# ct_frontend.net
KiCad netlist of a schematic drawn in Altium Designer
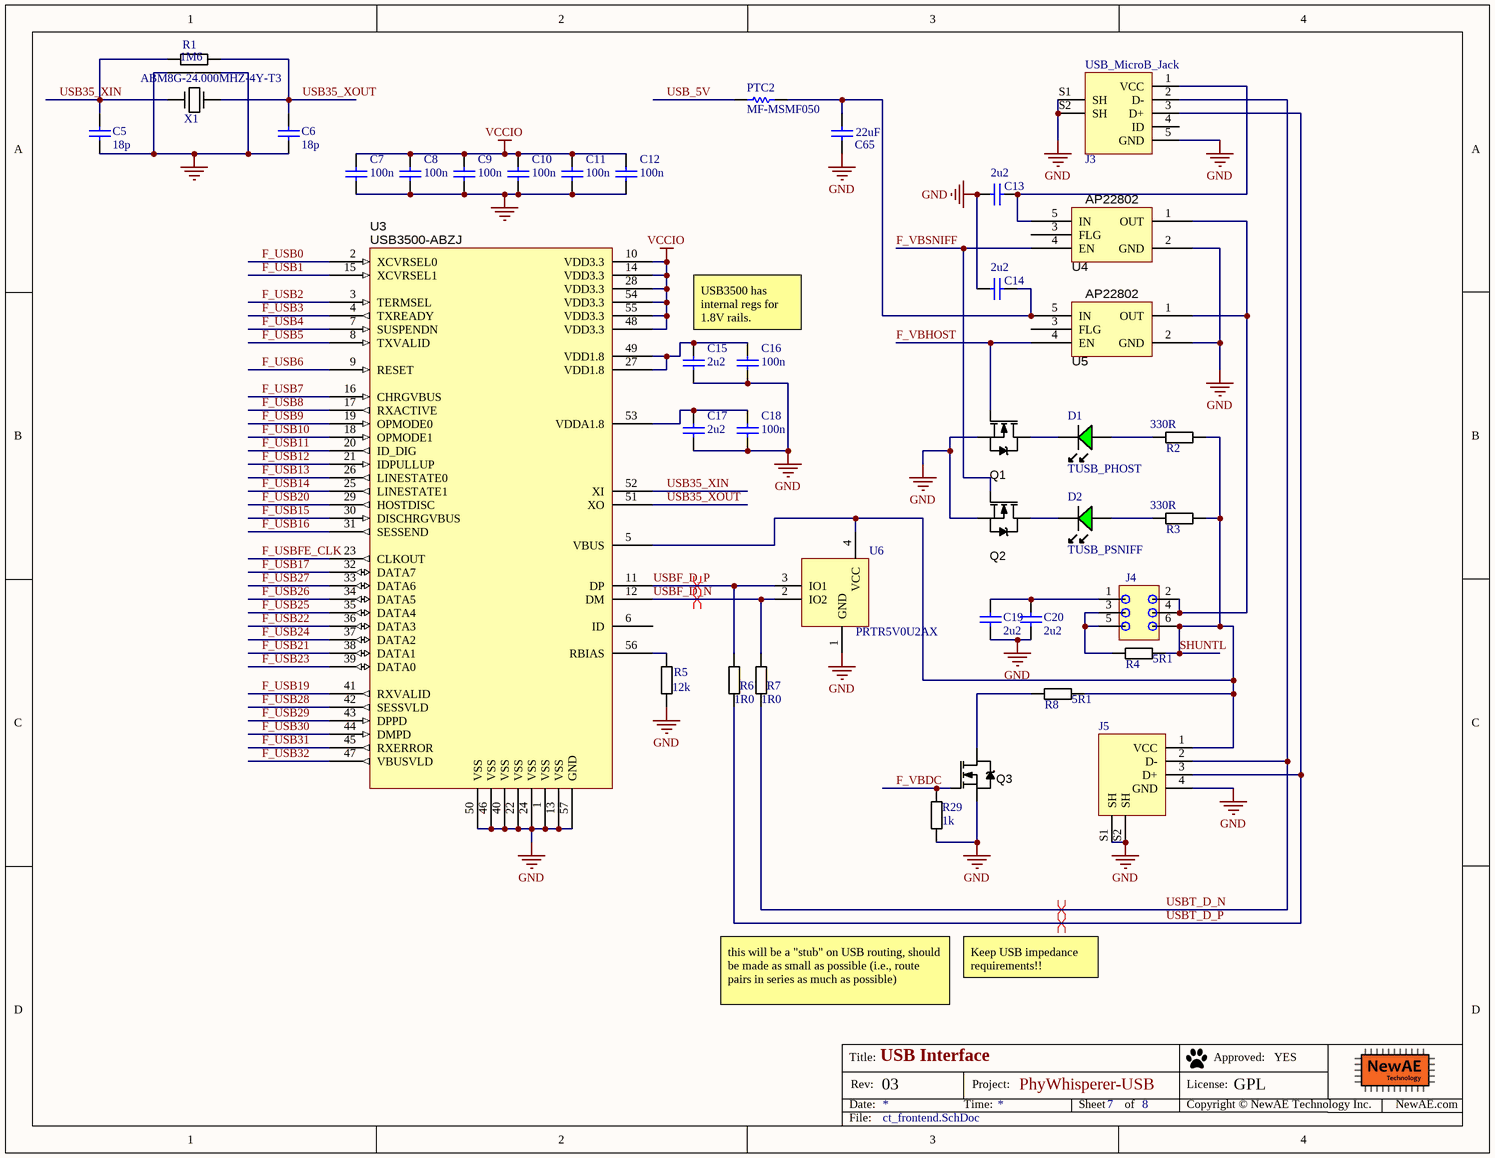
[diagram p0: ct_frontend.SchDoc]

(export (version "E")
  (design (tool "Eeschema 10.0.6"))
  (components
    (comp (ref "C5")
      (value "18p")
      (footprint "CAPC0402_M")
      (description "18p, 0402")
      (fields (field (name "PART NUMBER") "CCHIP-18p-0402"))
      (libsource (lib "NewAE_AltiumLib") (part "CAP"))
    )
    (comp (ref "C6")
      (value "18p")
      (footprint "CAPC0402_M")
      (description "18p, 0402")
      (fields (field (name "PART NUMBER") "CCHIP-18p-0402"))
      (libsource (lib "NewAE_AltiumLib") (part "CAP"))
    )
    (comp (ref "C7")
      (value "100n")
      (footprint "CAPC0603_M")
      (description "100n, 0603")
      (fields (field (name "PART NUMBER") "CCHIP-100n-0603"))
      (libsource (lib "NewAE_AltiumLib") (part "CAP"))
    )
    (comp (ref "C8")
      (value "100n")
      (footprint "CAPC0603_M")
      (description "100n, 0603")
      (fields (field (name "PART NUMBER") "CCHIP-100n-0603"))
      (libsource (lib "NewAE_AltiumLib") (part "CAP"))
    )
    (comp (ref "C9")
      (value "100n")
      (footprint "CAPC0603_M")
      (description "100n, 0603")
      (fields (field (name "PART NUMBER") "CCHIP-100n-0603"))
      (libsource (lib "NewAE_AltiumLib") (part "CAP"))
    )
    (comp (ref "C10")
      (value "100n")
      (footprint "CAPC0603_M")
      (description "100n, 0603")
      (fields (field (name "PART NUMBER") "CCHIP-100n-0603"))
      (libsource (lib "NewAE_AltiumLib") (part "CAP"))
    )
    (comp (ref "C11")
      (value "100n")
      (footprint "CAPC0603_M")
      (description "100n, 0603")
      (fields (field (name "PART NUMBER") "CCHIP-100n-0603"))
      (libsource (lib "NewAE_AltiumLib") (part "CAP"))
    )
    (comp (ref "C12")
      (value "100n")
      (footprint "CAPC0603_M")
      (description "100n, 0603")
      (fields (field (name "PART NUMBER") "CCHIP-100n-0603"))
      (libsource (lib "NewAE_AltiumLib") (part "CAP"))
    )
    (comp (ref "C13")
      (value "2u2")
      (footprint "CAPC0603_M")
      (description "2u2, 0603")
      (fields (field (name "PART NUMBER") "CCHIP-2u2-0603"))
      (libsource (lib "NewAE_AltiumLib") (part "CAP"))
    )
    (comp (ref "C14")
      (value "2u2")
      (footprint "CAPC0603_M")
      (description "2u2, 0603")
      (fields (field (name "PART NUMBER") "CCHIP-2u2-0603"))
      (libsource (lib "NewAE_AltiumLib") (part "CAP"))
    )
    (comp (ref "C15")
      (value "2u2")
      (footprint "CAPC0603_M")
      (description "2u2, 0603")
      (fields (field (name "PART NUMBER") "CCHIP-2u2-0603"))
      (libsource (lib "NewAE_AltiumLib") (part "CAP"))
    )
    (comp (ref "C16")
      (value "100n")
      (footprint "CAPC0603_M")
      (description "100n, 0603")
      (fields (field (name "PART NUMBER") "CCHIP-100n-0603"))
      (libsource (lib "NewAE_AltiumLib") (part "CAP"))
    )
    (comp (ref "C17")
      (value "2u2")
      (footprint "CAPC0603_M")
      (description "2u2, 0603")
      (fields (field (name "PART NUMBER") "CCHIP-2u2-0603"))
      (libsource (lib "NewAE_AltiumLib") (part "CAP"))
    )
    (comp (ref "C18")
      (value "100n")
      (footprint "CAPC0603_M")
      (description "100n, 0603")
      (fields (field (name "PART NUMBER") "CCHIP-100n-0603"))
      (libsource (lib "NewAE_AltiumLib") (part "CAP"))
    )
    (comp (ref "C19")
      (value "2u2")
      (footprint "CAPC0603_M")
      (description "2u2, 0603")
      (fields (field (name "PART NUMBER") "CCHIP-2u2-0603"))
      (libsource (lib "NewAE_AltiumLib") (part "CAP"))
    )
    (comp (ref "C20")
      (value "2u2")
      (footprint "CAPC0603_M")
      (description "2u2, 0603")
      (fields (field (name "PART NUMBER") "CCHIP-2u2-0603"))
      (libsource (lib "NewAE_AltiumLib") (part "CAP"))
    )
    (comp (ref "C65")
      (value "22uF")
      (footprint "CAPC0805_M")
      (description "22u, 16V, 0805, Ceramic")
      (fields (field (name "PART NUMBER") "CCHIP-22u-0805-16V") (field (name "TOLERANCE") "20%"))
      (libsource (lib "NewAE_AltiumLib") (part "CAP"))
    )
    (comp (ref "D1")
      (value "TUSB_PHOST")
      (footprint "LED-0603-GREEN")
      (description "Chip LED, Green")
      (fields (field (name "PART NUMBER") "LEDCHIP_0603_GREEN"))
      (libsource (lib "NewAE_AltiumLib") (part "LED_GREEN"))
    )
    (comp (ref "D2")
      (value "TUSB_PSNIFF")
      (footprint "LED-0603-GREEN")
      (description "Chip LED, Green")
      (fields (field (name "PART NUMBER") "LEDCHIP_0603_GREEN"))
      (libsource (lib "NewAE_AltiumLib") (part "LED_GREEN"))
    )
    (comp (ref "J3")
      (value "USB_MicroB_Jack")
      (footprint "ZX62D-B-5P8(30)")
      (description "CONN RCPT USB MICRO B SMD")
      (fields (field (name "PART NUMBER") "ZX62D-B-5P8(30)"))
      (libsource (lib "NewAE_AltiumLib") (part "USB_5PIN_2SHIELD"))
    )
    (comp (ref "J4")
      (value "TSW-103-08-F-D-RA")
      (footprint "HDR_6PIN_2ROW_RA_UNSHROUDED")
      (description "2x3 Header, R/A, Unshrouded")
      (fields (field (name "PART NUMBER") "HDR_6PIN_2ROW_RA_UNSHROUDED"))
      (libsource (lib "NewAE_AltiumLib") (part "CON6_2ROW"))
    )
    (comp (ref "J5")
      (value "USB-A-S-F-W-TH")
      (footprint "USB-A-S-F-W-TH")
      (description "Female USB-A")
      (libsource (lib "NewAE_AltiumLib") (part "USB_4PIN_2SHIELD"))
    )
    (comp (ref "PTC2")
      (value "MF-MSMF050")
      (footprint "BOUR-MF-MSMF050-2_V")
      (description "MF-MSMF Series - PTC Resettable Fuse, 15 V Max, 0.15 Ohm Min, -40 to 85 degC, RoHS, Reel")
      (fields (field (name "MANUFACTURER") "Bourns"))
      (libsource (lib "Altium Content Vault") (part "CMP-0280-00002-2"))
    )
    (comp (ref "Q1")
      (value "DMN3200U-7")
      (footprint "SOT95P245X110-3M")
      (description "MOSFET N-CH 30V 2.2A SOT23-3")
      (libsource (lib "NewAE_AltiumLib") (part "MOSFET_N_GSD"))
    )
    (comp (ref "Q2")
      (value "DMN3200U-7")
      (footprint "SOT95P245X110-3M")
      (description "MOSFET N-CH 30V 2.2A SOT23-3")
      (libsource (lib "NewAE_AltiumLib") (part "MOSFET_N_GSD"))
    )
    (comp (ref "Q3")
      (value "DMN3200U-7")
      (footprint "SOT95P245X110-3M")
      (description "MOSFET N-CH 30V 2.2A SOT23-3")
      (libsource (lib "NewAE_AltiumLib") (part "MOSFET_N_GSD"))
    )
    (comp (ref "R1")
      (value "1M6")
      (footprint "RESC1608X55N")
      (description "1M6 res, 0603, 1%, 1/10W")
      (fields (field (name "PART NUMBER") "RCHIP-1M6-0603") (field (name "TOLERANCE") "1%"))
      (libsource (lib "NewAE_AltiumLib") (part "RES-EU"))
    )
    (comp (ref "R2")
      (value "330R")
      (footprint "RESC1608X55N")
      (description "330R res, 0603, 1%, 1/10W")
      (fields (field (name "PART NUMBER") "RCHIP-330R-0603") (field (name "TOLERANCE") "1%"))
      (libsource (lib "NewAE_AltiumLib") (part "RES-EU"))
    )
    (comp (ref "R3")
      (value "330R")
      (footprint "RESC1608X55N")
      (description "330R res, 0603, 1%, 1/10W")
      (fields (field (name "PART NUMBER") "RCHIP-330R-0603") (field (name "TOLERANCE") "1%"))
      (libsource (lib "NewAE_AltiumLib") (part "RES-EU"))
    )
    (comp (ref "R4")
      (value "5R1")
      (footprint "RESC2012X70N")
      (description "5R1  res, 0805, 1%")
      (fields (field (name "PART NUMBER") "RCHIP-5R1-0805"))
      (libsource (lib "NewAE_AltiumLib") (part "RES-EU"))
    )
    (comp (ref "R5")
      (value "12k")
      (footprint "RESC1608X55N")
      (description "12k res, 0603, 1%, 1/10W")
      (fields (field (name "PART NUMBER") "RCHIP-12K-0603") (field (name "TOLERANCE") "1%"))
      (libsource (lib "") (part "RES-EU_1"))
    )
    (comp (ref "R6")
      (value "1R0")
      (footprint "RESC1608X55N")
      (description "1R0 res, 0603, 1%, 1/10W")
      (fields (field (name "PART NUMBER") "RCHIP-1R0-0603") (field (name "TOLERANCE") "1%"))
      (libsource (lib "") (part "RES-EU_1"))
    )
    (comp (ref "R7")
      (value "1R0")
      (footprint "RESC1608X55N")
      (description "1R0 res, 0603, 1%, 1/10W")
      (fields (field (name "PART NUMBER") "RCHIP-1R0-0603") (field (name "TOLERANCE") "1%"))
      (libsource (lib "") (part "RES-EU_1"))
    )
    (comp (ref "R8")
      (value "5R1")
      (footprint "RESC2012X70N")
      (description "5R1  res, 0805, 1%")
      (fields (field (name "PART NUMBER") "RCHIP-5R1-0805"))
      (libsource (lib "NewAE_AltiumLib") (part "RES-EU"))
    )
    (comp (ref "R29")
      (value "1k")
      (footprint "RESC1608X55N")
      (description "1k res, 0603, 1%, 1/10W")
      (fields (field (name "PART NUMBER") "RCHIP-1K-0603") (field (name "TOLERANCE") "1%"))
      (libsource (lib "") (part "RES-EU_2"))
    )
    (comp (ref "U3")
      (value "USB3500-ABZJ")
      (footprint "QFN50P800X800X100_HS-57M")
      (description "USB Phy, UTMI 3+")
      (fields (field (name "PART NUMBER") "USB3500") (field (name "CREATED BY") "D.GODDARD"))
      (libsource (lib "NewAE_AltiumLib") (part "USB3500"))
    )
    (comp (ref "U4")
      (value "AP22802")
      (footprint "SOT23-5P95_285X145L45X40")
      (description "USB Power Switch, Digital IC")
      (fields (field (name "CREATED BY") "D.GODDARD"))
      (libsource (lib "NewAE_AltiumLib") (part "AP22802"))
    )
    (comp (ref "U5")
      (value "AP22802")
      (footprint "SOT23-5P95_285X145L45X40")
      (description "USB Power Switch, Digital IC")
      (fields (field (name "CREATED BY") "D.GODDARD"))
      (libsource (lib "NewAE_AltiumLib") (part "AP22802"))
    )
    (comp (ref "U6")
      (value "PRTR5V0U2AX")
      (footprint "SOT143B")
      (description "USB 2.0 high-speed ESD")
      (libsource (lib "NewAE_AltiumLib") (part "PRTR5V0U2AX"))
    )
    (comp (ref "X1")
      (value "ABM8G-24.000MHZ-4Y-T3")
      (footprint "ABM8G")
      (description "CRYSTAL 24.0000MHZ 10PF SMD")
      (libsource (lib "NewAE_AltiumLib") (part "XTAL_4PIN_13"))
    )
  )
  (nets
    (net (code "1") (name "/F_USB0") (class "Default")
      (node (ref "U3") (pin "2") (pinfunction "XCVRSEL0_2") (pintype "input"))
    )
    (net (code "2") (name "/F_USB1") (class "Default")
      (node (ref "U3") (pin "15") (pinfunction "XCVRSEL1_15") (pintype "input"))
    )
    (net (code "3") (name "/F_USB2") (class "Default")
      (node (ref "U3") (pin "3") (pinfunction "TERMSEL_3") (pintype "input"))
    )
    (net (code "4") (name "/F_USB3") (class "Default")
      (node (ref "U3") (pin "4") (pinfunction "TXREADY_4") (pintype "output"))
    )
    (net (code "5") (name "/F_USB4") (class "Default")
      (node (ref "U3") (pin "7") (pinfunction "SUSPENDN_7") (pintype "input"))
    )
    (net (code "6") (name "/F_USB5") (class "Default")
      (node (ref "U3") (pin "8") (pinfunction "TXVALID_8") (pintype "input"))
    )
    (net (code "7") (name "/F_USB6") (class "Default")
      (node (ref "U3") (pin "9") (pinfunction "RESET_9") (pintype "input"))
    )
    (net (code "8") (name "/F_USB7") (class "Default")
      (node (ref "U3") (pin "16") (pinfunction "CHRGVBUS_16") (pintype "input"))
    )
    (net (code "9") (name "/F_USB8") (class "Default")
      (node (ref "U3") (pin "17") (pinfunction "RXACTIVE_17") (pintype "output"))
    )
    (net (code "10") (name "/F_USB9") (class "Default")
      (node (ref "U3") (pin "19") (pinfunction "OPMODE0_19") (pintype "input"))
    )
    (net (code "11") (name "/F_USB10") (class "Default")
      (node (ref "U3") (pin "18") (pinfunction "OPMODE1_18") (pintype "input"))
    )
    (net (code "12") (name "/F_USB11") (class "Default")
      (node (ref "U3") (pin "20") (pinfunction "ID_DIG_20") (pintype "output"))
    )
    (net (code "13") (name "/F_USB12") (class "Default")
      (node (ref "U3") (pin "21") (pinfunction "IDPULLUP_21") (pintype "input"))
    )
    (net (code "14") (name "/F_USB13") (class "Default")
      (node (ref "U3") (pin "26") (pinfunction "LINESTATE0_26") (pintype "output"))
    )
    (net (code "15") (name "/F_USB14") (class "Default")
      (node (ref "U3") (pin "25") (pinfunction "LINESTATE1_25") (pintype "output"))
    )
    (net (code "16") (name "/F_USB15") (class "Default")
      (node (ref "U3") (pin "30") (pinfunction "DISCHRGVBUS_30") (pintype "input"))
    )
    (net (code "17") (name "/F_USB16") (class "Default")
      (node (ref "U3") (pin "31") (pinfunction "SESSEND_31") (pintype "output"))
    )
    (net (code "18") (name "/F_USB17") (class "Default")
      (node (ref "U3") (pin "32") (pinfunction "DATA7_32") (pintype "bidirectional"))
    )
    (net (code "19") (name "/F_USB19") (class "Default")
      (node (ref "U3") (pin "41") (pinfunction "RXVALID_41") (pintype "output"))
    )
    (net (code "20") (name "/F_USB20") (class "Default")
      (node (ref "U3") (pin "29") (pinfunction "HOSTDISC_29") (pintype "output"))
    )
    (net (code "21") (name "/F_USB21") (class "Default")
      (node (ref "U3") (pin "38") (pinfunction "DATA1_38") (pintype "bidirectional"))
    )
    (net (code "22") (name "/F_USB22") (class "Default")
      (node (ref "U3") (pin "36") (pinfunction "DATA3_36") (pintype "bidirectional"))
    )
    (net (code "23") (name "/F_USB23") (class "Default")
      (node (ref "U3") (pin "39") (pinfunction "DATA0_39") (pintype "bidirectional"))
    )
    (net (code "24") (name "/F_USB24") (class "Default")
      (node (ref "U3") (pin "37") (pinfunction "DATA2_37") (pintype "bidirectional"))
    )
    (net (code "25") (name "/F_USB25") (class "Default")
      (node (ref "U3") (pin "35") (pinfunction "DATA4_35") (pintype "bidirectional"))
    )
    (net (code "26") (name "/F_USB26") (class "Default")
      (node (ref "U3") (pin "34") (pinfunction "DATA5_34") (pintype "bidirectional"))
    )
    (net (code "27") (name "/F_USB27") (class "Default")
      (node (ref "U3") (pin "33") (pinfunction "DATA6_33") (pintype "bidirectional"))
    )
    (net (code "28") (name "/F_USB28") (class "Default")
      (node (ref "U3") (pin "42") (pinfunction "SESSVLD_42") (pintype "output"))
    )
    (net (code "29") (name "/F_USB29") (class "Default")
      (node (ref "U3") (pin "43") (pinfunction "DPPD_43") (pintype "input"))
    )
    (net (code "30") (name "/F_USB30") (class "Default")
      (node (ref "U3") (pin "44") (pinfunction "DMPD_44") (pintype "input"))
    )
    (net (code "31") (name "/F_USB31") (class "Default")
      (node (ref "U3") (pin "45") (pinfunction "RXERROR_45") (pintype "output"))
    )
    (net (code "32") (name "/F_USB32") (class "Default")
      (node (ref "U3") (pin "47") (pinfunction "VBUSVLD_47") (pintype "output"))
    )
    (net (code "33") (name "/F_USBFE_CLK") (class "Default")
      (node (ref "U3") (pin "23") (pinfunction "CLKOUT_23") (pintype "output"))
    )
    (net (code "34") (name "/F_VBDC") (class "Default")
      (node (ref "Q3") (pin "1") (pinfunction "G_1") (pintype "passive"))
      (node (ref "R29") (pin "2") (pinfunction "2_2") (pintype "passive"))
    )
    (net (code "35") (name "/F_VBHOST") (class "Default")
      (node (ref "Q1") (pin "1") (pinfunction "G_1") (pintype "passive"))
      (node (ref "U5") (pin "4") (pinfunction "EN_4") (pintype "passive"))
    )
    (net (code "36") (name "/F_VBSNIFF") (class "Default")
      (node (ref "Q2") (pin "1") (pinfunction "G_1") (pintype "passive"))
      (node (ref "U4") (pin "4") (pinfunction "EN_4") (pintype "passive"))
    )
    (net (code "37") (name "/SHUNTL") (class "Default")
      (node (ref "J4") (pin "6") (pinfunction "6_6") (pintype "passive"))
      (node (ref "J5") (pin "1") (pinfunction "VCC_1") (pintype "passive"))
      (node (ref "R2") (pin "2") (pinfunction "2_2") (pintype "passive"))
      (node (ref "R3") (pin "2") (pinfunction "2_2") (pintype "passive"))
      (node (ref "R4") (pin "2") (pinfunction "2_2") (pintype "passive"))
      (node (ref "R8") (pin "2") (pinfunction "2_2") (pintype "passive"))
      (node (ref "U3") (pin "5") (pinfunction "VBUS_5") (pintype "passive"))
      (node (ref "U6") (pin "4") (pinfunction "VCC_4") (pintype "power_in"))
    )
    (net (code "38") (name "/USB35_XIN") (class "Default")
      (node (ref "C5") (pin "1") (pinfunction "1_1") (pintype "passive"))
      (node (ref "R1") (pin "1") (pinfunction "1_1") (pintype "passive"))
      (node (ref "U3") (pin "52") (pinfunction "XI_52") (pintype "passive"))
      (node (ref "X1") (pin "1") (pinfunction "IN_1") (pintype "passive"))
    )
    (net (code "39") (name "/USB35_XOUT") (class "Default")
      (node (ref "C6") (pin "1") (pinfunction "1_1") (pintype "passive"))
      (node (ref "R1") (pin "2") (pinfunction "2_2") (pintype "passive"))
      (node (ref "U3") (pin "51") (pinfunction "XO_51") (pintype "passive"))
      (node (ref "X1") (pin "3") (pinfunction "OUT_3") (pintype "passive"))
    )
    (net (code "40") (name "/USBF_D_N") (class "Default")
      (node (ref "R7") (pin "1") (pinfunction "1_1") (pintype "passive"))
      (node (ref "U3") (pin "12") (pinfunction "DM_12") (pintype "passive"))
      (node (ref "U6") (pin "2") (pinfunction "IO2_2") (pintype "power_in"))
    )
    (net (code "41") (name "/USBF_D_P") (class "Default")
      (node (ref "R6") (pin "1") (pinfunction "1_1") (pintype "passive"))
      (node (ref "U3") (pin "11") (pinfunction "DP_11") (pintype "passive"))
      (node (ref "U6") (pin "3") (pinfunction "IO1_3") (pintype "power_in"))
    )
    (net (code "42") (name "/USBT_D_N") (class "Default")
      (node (ref "J3") (pin "2") (pinfunction "D-_2") (pintype "passive"))
      (node (ref "J5") (pin "2") (pinfunction "D-_2") (pintype "passive"))
      (node (ref "R7") (pin "2") (pinfunction "2_2") (pintype "passive"))
    )
    (net (code "43") (name "/USBT_D_P") (class "Default")
      (node (ref "J3") (pin "3") (pinfunction "D+_3") (pintype "passive"))
      (node (ref "J5") (pin "3") (pinfunction "D+_3") (pintype "passive"))
      (node (ref "R6") (pin "2") (pinfunction "2_2") (pintype "passive"))
    )
    (net (code "44") (name "/USB_5V") (class "Default")
      (node (ref "PTC2") (pin "1") (pinfunction "1_1") (pintype "passive"))
    )
    (net (code "45") (name "GND") (class "Default")
      (node (ref "C10") (pin "2") (pinfunction "2_2") (pintype "passive"))
      (node (ref "C11") (pin "2") (pinfunction "2_2") (pintype "passive"))
      (node (ref "C12") (pin "2") (pinfunction "2_2") (pintype "passive"))
      (node (ref "C13") (pin "1") (pinfunction "1_1") (pintype "passive"))
      (node (ref "C14") (pin "1") (pinfunction "1_1") (pintype "passive"))
      (node (ref "C15") (pin "2") (pinfunction "2_2") (pintype "passive"))
      (node (ref "C16") (pin "2") (pinfunction "2_2") (pintype "passive"))
      (node (ref "C17") (pin "2") (pinfunction "2_2") (pintype "passive"))
      (node (ref "C18") (pin "2") (pinfunction "2_2") (pintype "passive"))
      (node (ref "C19") (pin "1") (pinfunction "1_1") (pintype "passive"))
      (node (ref "C20") (pin "1") (pinfunction "1_1") (pintype "passive"))
      (node (ref "C5") (pin "2") (pinfunction "2_2") (pintype "passive"))
      (node (ref "C6") (pin "2") (pinfunction "2_2") (pintype "passive"))
      (node (ref "C65") (pin "2") (pinfunction "2_2") (pintype "passive"))
      (node (ref "C7") (pin "2") (pinfunction "2_2") (pintype "passive"))
      (node (ref "C8") (pin "2") (pinfunction "2_2") (pintype "passive"))
      (node (ref "C9") (pin "2") (pinfunction "2_2") (pintype "passive"))
      (node (ref "J3") (pin "5") (pinfunction "GND_5") (pintype "power_in"))
      (node (ref "J3") (pin "S1") (pinfunction "SH_S1") (pintype "passive"))
      (node (ref "J3") (pin "S2") (pinfunction "SH_S2") (pintype "passive"))
      (node (ref "J5") (pin "4") (pinfunction "GND_4") (pintype "power_in"))
      (node (ref "J5") (pin "S1") (pinfunction "SH_S1") (pintype "passive"))
      (node (ref "J5") (pin "S2") (pinfunction "SH_S2") (pintype "passive"))
      (node (ref "Q1") (pin "2") (pinfunction "S_2") (pintype "passive"))
      (node (ref "Q2") (pin "2") (pinfunction "S_2") (pintype "passive"))
      (node (ref "Q3") (pin "2") (pinfunction "S_2") (pintype "passive"))
      (node (ref "R29") (pin "1") (pinfunction "1_1") (pintype "passive"))
      (node (ref "R5") (pin "2") (pinfunction "2_2") (pintype "passive"))
      (node (ref "U3") (pin "1") (pinfunction "VSS_1") (pintype "passive"))
      (node (ref "U3") (pin "13") (pinfunction "VSS_13") (pintype "passive"))
      (node (ref "U3") (pin "22") (pinfunction "VSS_22") (pintype "passive"))
      (node (ref "U3") (pin "24") (pinfunction "VSS_24") (pintype "passive"))
      (node (ref "U3") (pin "40") (pinfunction "VSS_40") (pintype "passive"))
      (node (ref "U3") (pin "46") (pinfunction "VSS_46") (pintype "passive"))
      (node (ref "U3") (pin "50") (pinfunction "VSS_50") (pintype "passive"))
      (node (ref "U3") (pin "57") (pinfunction "GND_57") (pintype "passive"))
      (node (ref "U4") (pin "2") (pinfunction "GND_2") (pintype "passive"))
      (node (ref "U5") (pin "2") (pinfunction "GND_2") (pintype "passive"))
      (node (ref "U6") (pin "1") (pinfunction "GND_1") (pintype "power_in"))
      (node (ref "X1") (pin "2") (pinfunction "GND_2") (pintype "power_in"))
      (node (ref "X1") (pin "4") (pinfunction "GND_4") (pintype "power_in"))
    )
    (net (code "46") (name "Net-(C15-Pad1)") (class "Default")
      (node (ref "C15") (pin "1") (pinfunction "1_1") (pintype "passive"))
      (node (ref "C16") (pin "1") (pinfunction "1_1") (pintype "passive"))
      (node (ref "U3") (pin "27") (pinfunction "VDD1.8_27") (pintype "passive"))
      (node (ref "U3") (pin "49") (pinfunction "VDD1.8_49") (pintype "passive"))
    )
    (net (code "47") (name "Net-(C19-Pad2)") (class "Default")
      (node (ref "C19") (pin "2") (pinfunction "2_2") (pintype "passive"))
      (node (ref "C20") (pin "2") (pinfunction "2_2") (pintype "passive"))
      (node (ref "J4") (pin "1") (pinfunction "1_1") (pintype "passive"))
    )
    (net (code "48") (name "Net-(D1-PadA)") (class "Default")
      (node (ref "D1") (pin "A") (pinfunction "A_A") (pintype "passive"))
      (node (ref "R2") (pin "1") (pinfunction "1_1") (pintype "passive"))
    )
    (net (code "49") (name "Net-(D2-PadA)") (class "Default")
      (node (ref "D2") (pin "A") (pinfunction "A_A") (pintype "passive"))
      (node (ref "R3") (pin "1") (pinfunction "1_1") (pintype "passive"))
    )
    (net (code "50") (name "Net-(J3-VCC)") (class "Default")
      (node (ref "C13") (pin "2") (pinfunction "2_2") (pintype "passive"))
      (node (ref "J3") (pin "1") (pinfunction "VCC_1") (pintype "passive"))
      (node (ref "U4") (pin "5") (pinfunction "IN_5") (pintype "passive"))
    )
    (net (code "51") (name "Net-(J4-Pad3)") (class "Default")
      (node (ref "J4") (pin "3") (pinfunction "3_3") (pintype "passive"))
      (node (ref "J4") (pin "5") (pinfunction "5_5") (pintype "passive"))
      (node (ref "R4") (pin "1") (pinfunction "1_1") (pintype "passive"))
    )
    (net (code "52") (name "Net-(Q1-D)") (class "Default")
      (node (ref "D1") (pin "K") (pinfunction "K_K") (pintype "passive"))
      (node (ref "Q1") (pin "3") (pinfunction "D_3") (pintype "passive"))
    )
    (net (code "53") (name "Net-(Q2-D)") (class "Default")
      (node (ref "D2") (pin "K") (pinfunction "K_K") (pintype "passive"))
      (node (ref "Q2") (pin "3") (pinfunction "D_3") (pintype "passive"))
    )
    (net (code "54") (name "Net-(Q3-D)") (class "Default")
      (node (ref "Q3") (pin "3") (pinfunction "D_3") (pintype "passive"))
      (node (ref "R8") (pin "1") (pinfunction "1_1") (pintype "passive"))
    )
    (net (code "55") (name "Net-(U3-RBIAS)") (class "Default")
      (node (ref "R5") (pin "1") (pinfunction "1_1") (pintype "passive"))
      (node (ref "U3") (pin "56") (pinfunction "RBIAS_56") (pintype "passive"))
    )
    (net (code "56") (name "Net-(U3-VDDA1.8)") (class "Default")
      (node (ref "C17") (pin "1") (pinfunction "1_1") (pintype "passive"))
      (node (ref "C18") (pin "1") (pinfunction "1_1") (pintype "passive"))
      (node (ref "U3") (pin "53") (pinfunction "VDDA1.8_53") (pintype "passive"))
    )
    (net (code "57") (name "Net-(U4-OUT)") (class "Default")
      (node (ref "J4") (pin "2") (pinfunction "2_2") (pintype "passive"))
      (node (ref "J4") (pin "4") (pinfunction "4_4") (pintype "passive"))
      (node (ref "U4") (pin "1") (pinfunction "OUT_1") (pintype "passive"))
      (node (ref "U5") (pin "1") (pinfunction "OUT_1") (pintype "passive"))
    )
    (net (code "58") (name "Net-(U5-IN)") (class "Default")
      (node (ref "C14") (pin "2") (pinfunction "2_2") (pintype "passive"))
      (node (ref "C65") (pin "1") (pinfunction "1_1") (pintype "passive"))
      (node (ref "PTC2") (pin "2") (pinfunction "2_2") (pintype "passive"))
      (node (ref "U5") (pin "5") (pinfunction "IN_5") (pintype "passive"))
    )
    (net (code "59") (name "VCCIO") (class "Default")
      (node (ref "C10") (pin "1") (pinfunction "1_1") (pintype "passive"))
      (node (ref "C11") (pin "1") (pinfunction "1_1") (pintype "passive"))
      (node (ref "C12") (pin "1") (pinfunction "1_1") (pintype "passive"))
      (node (ref "C7") (pin "1") (pinfunction "1_1") (pintype "passive"))
      (node (ref "C8") (pin "1") (pinfunction "1_1") (pintype "passive"))
      (node (ref "C9") (pin "1") (pinfunction "1_1") (pintype "passive"))
      (node (ref "U3") (pin "10") (pinfunction "VDD3.3_10") (pintype "passive"))
      (node (ref "U3") (pin "14") (pinfunction "VDD3.3_14") (pintype "passive"))
      (node (ref "U3") (pin "28") (pinfunction "VDD3.3_28") (pintype "passive"))
      (node (ref "U3") (pin "48") (pinfunction "VDD3.3_48") (pintype "passive"))
      (node (ref "U3") (pin "54") (pinfunction "VDD3.3_54") (pintype "passive"))
      (node (ref "U3") (pin "55") (pinfunction "VDD3.3_55") (pintype "passive"))
    )
    (net (code "60") (name "unconnected-(J3-ID-Pad4)") (class "Default")
      (node (ref "J3") (pin "4") (pinfunction "ID_4") (pintype "power_in"))
    )
    (net (code "61") (name "unconnected-(U3-ID-Pad6)") (class "Default")
      (node (ref "U3") (pin "6") (pinfunction "ID_6") (pintype "passive"))
    )
    (net (code "62") (name "unconnected-(U4-FLG-Pad3)") (class "Default")
      (node (ref "U4") (pin "3") (pinfunction "FLG_3") (pintype "passive"))
    )
    (net (code "63") (name "unconnected-(U5-FLG-Pad3)") (class "Default")
      (node (ref "U5") (pin "3") (pinfunction "FLG_3") (pintype "passive"))
    )
  )
)
